# BaseMod.net
KiCad netlist of a schematic drawn in Altium Designer
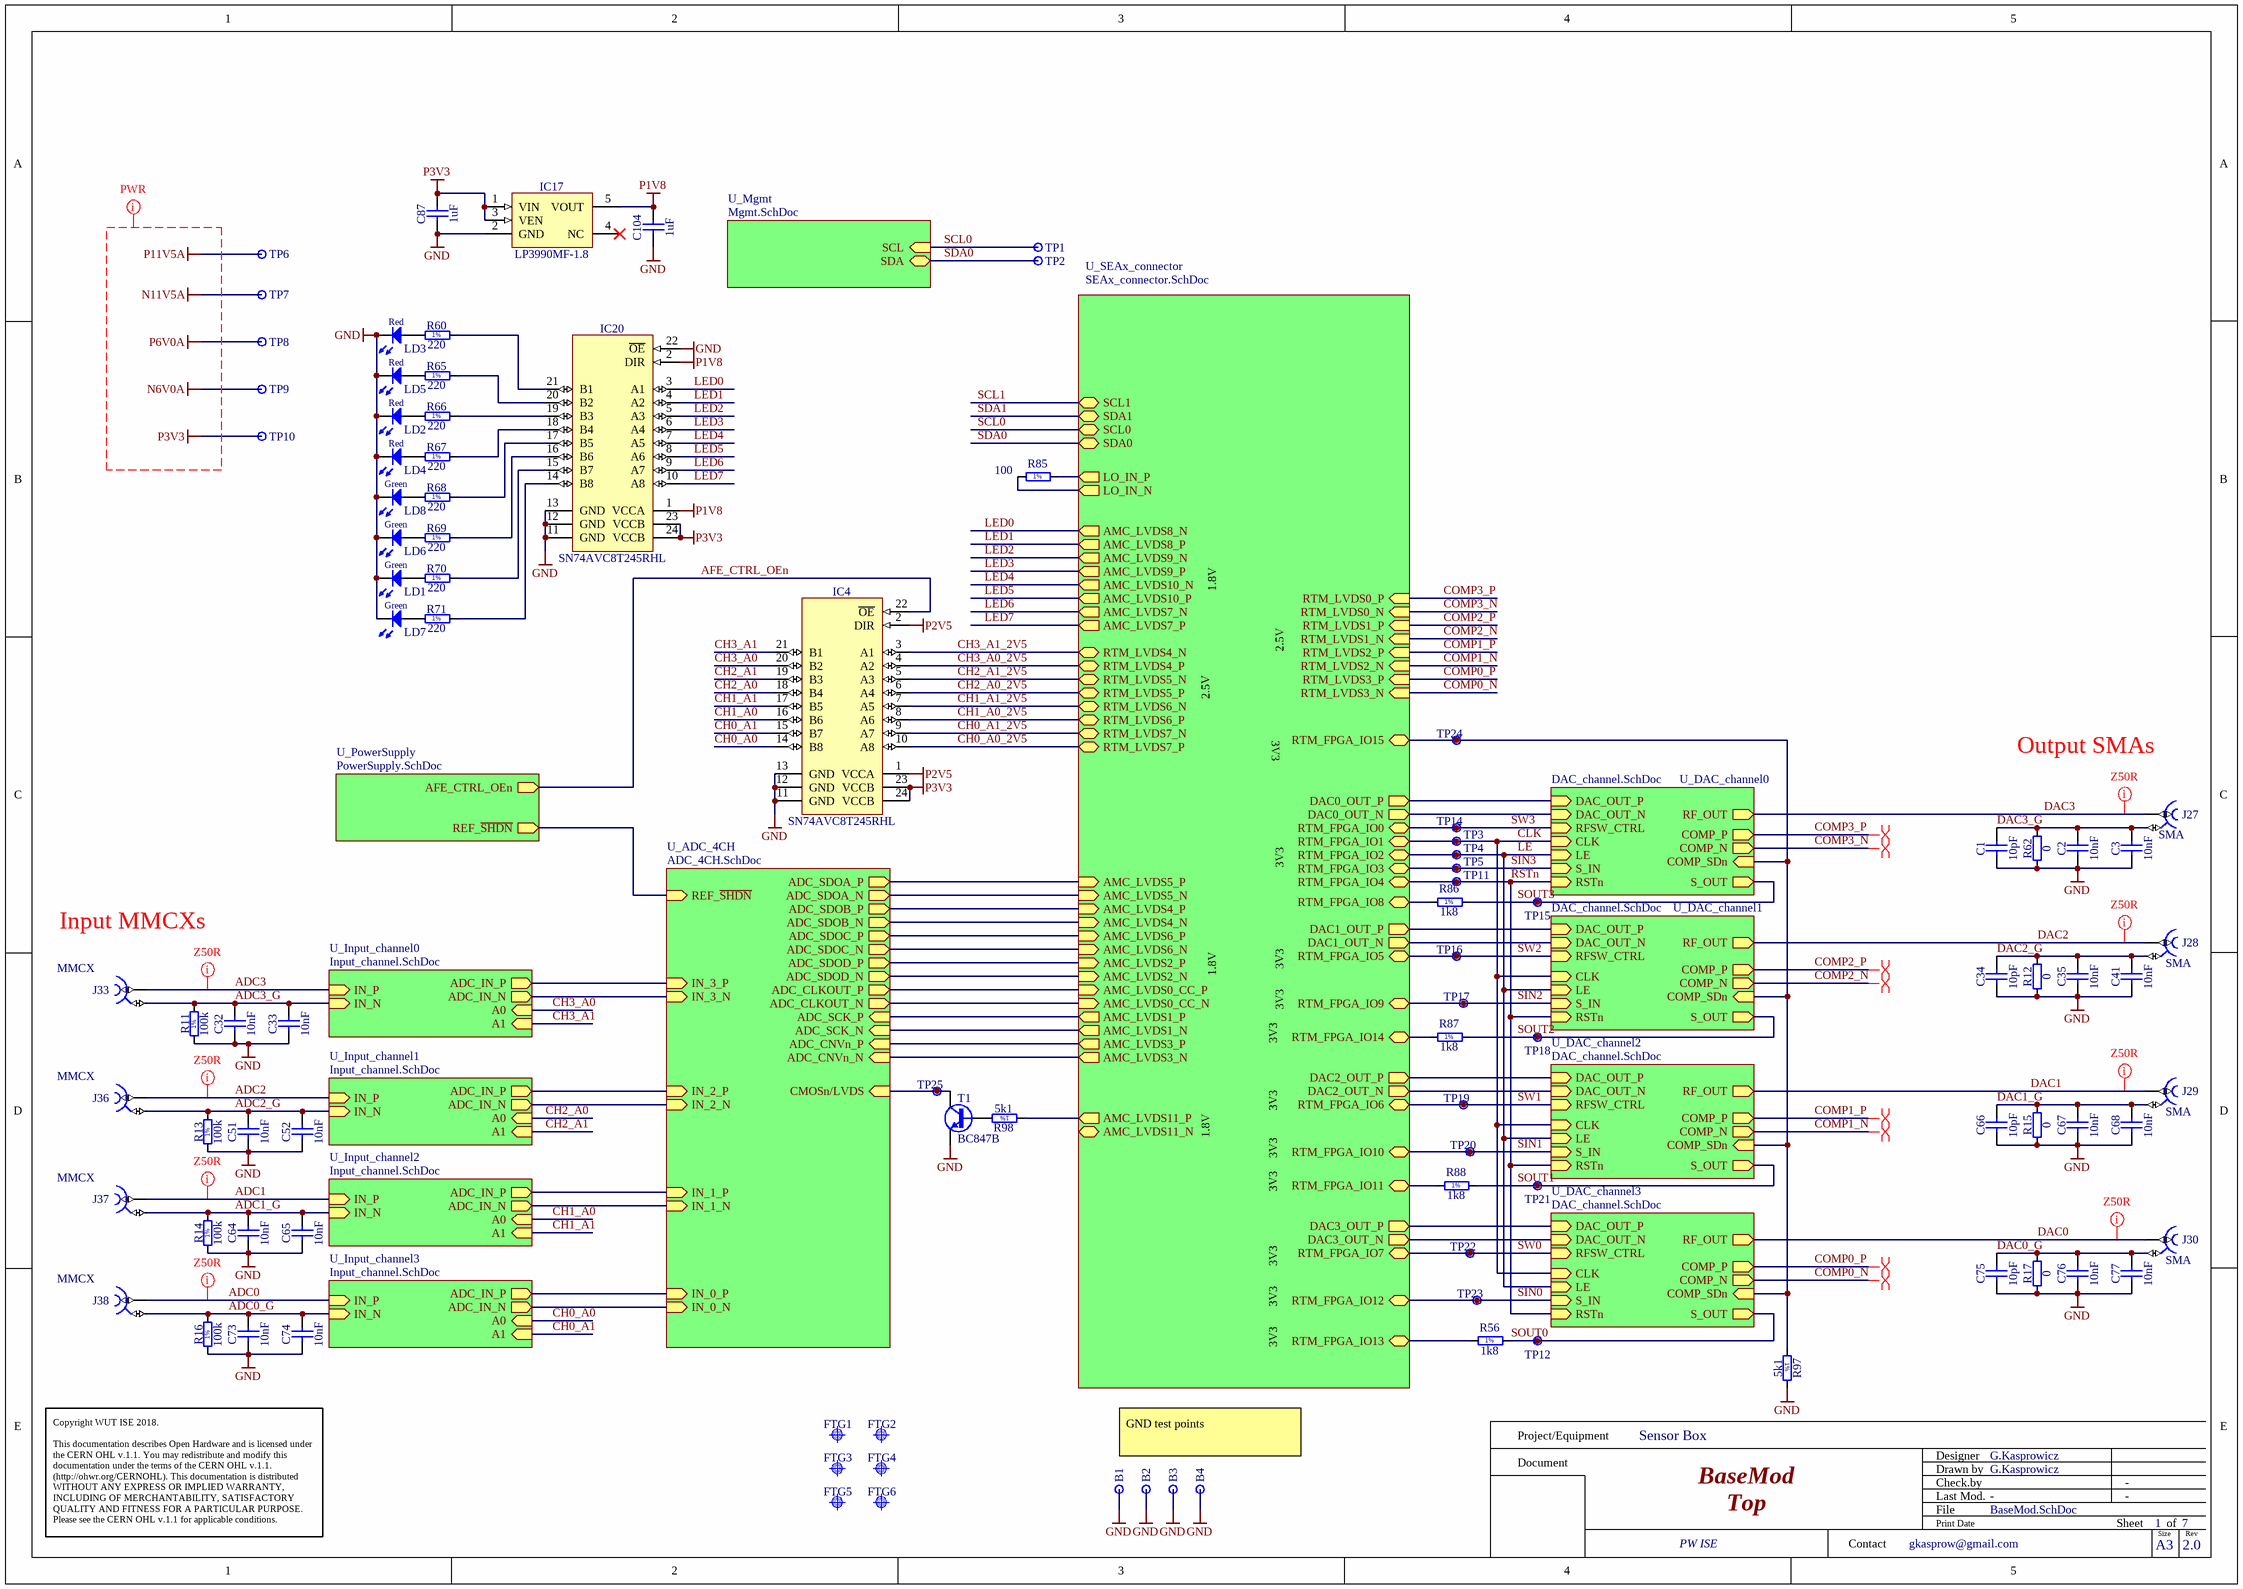
[diagram p0: BaseMod.SchDoc]

(export (version "E")
  (design (tool "Eeschema 10.0.6"))
  (components
    (comp (ref "B1")
      (value "Plated Hole")
      (footprint "c130h80")
      (description "Single Terminal Socket")
      (fields (field (name "PART NUMBER") "PLATED_HOLE0.8_PAD1.3") (field (name "AUTHOR") "CERN DEM JLC"))
      (libsource (lib "Eletro-mechanical") (part "Single Terminal Socket"))
    )
    (comp (ref "B2")
      (value "Plated Hole")
      (footprint "c130h80")
      (description "Single Terminal Socket")
      (fields (field (name "PART NUMBER") "PLATED_HOLE0.8_PAD1.3") (field (name "AUTHOR") "CERN DEM JLC"))
      (libsource (lib "Eletro-mechanical") (part "Single Terminal Socket"))
    )
    (comp (ref "B3")
      (value "Plated Hole")
      (footprint "c130h80")
      (description "Single Terminal Socket")
      (fields (field (name "PART NUMBER") "PLATED_HOLE0.8_PAD1.3") (field (name "AUTHOR") "CERN DEM JLC"))
      (libsource (lib "Eletro-mechanical") (part "Single Terminal Socket"))
    )
    (comp (ref "B4")
      (value "Plated Hole")
      (footprint "c130h80")
      (description "Single Terminal Socket")
      (fields (field (name "PART NUMBER") "PLATED_HOLE0.8_PAD1.3") (field (name "AUTHOR") "CERN DEM JLC"))
      (libsource (lib "Eletro-mechanical") (part "Single Terminal Socket"))
    )
    (comp (ref "C1")
      (value "10pF")
      (footprint "CAPC1005X55N")
      (description "Non-polarised capacitor")
      (fields
        (field (name "PART NUMBER") "CC0402_10PF_50V_5%_C0G")
        (field (name "VOLTAGE") "50V")
        (field (name "AUTHOR") "CERN DEM JLC")
      )
      (libsource (lib "Capacitors") (part "Capacitor - non polarized"))
    )
    (comp (ref "C2")
      (value "10nF")
      (footprint "CAPC1005X55N")
      (description "Non-polarised capacitor")
      (fields
        (field (name "PART NUMBER") "CC0402_10NF_16V_10%_X7R")
        (field (name "VOLTAGE") "16V")
        (field (name "AUTHOR") "CERN DEM JLC")
      )
      (libsource (lib "Capacitors") (part "Capacitor - non polarized"))
    )
    (comp (ref "C3")
      (value "10nF")
      (footprint "CAPC1005X55N")
      (description "Non-polarised capacitor")
      (fields
        (field (name "PART NUMBER") "CC0402_10NF_16V_10%_X7R")
        (field (name "VOLTAGE") "16V")
        (field (name "AUTHOR") "CERN DEM JLC")
      )
      (libsource (lib "Capacitors") (part "Capacitor - non polarized"))
    )
    (comp (ref "C32")
      (value "10nF")
      (footprint "CAPC1005X55N")
      (description "Non-polarised capacitor")
      (fields
        (field (name "PART NUMBER") "CC0402_10NF_16V_10%_X7R")
        (field (name "VOLTAGE") "16V")
        (field (name "AUTHOR") "CERN DEM JLC")
      )
      (libsource (lib "Capacitors") (part "Capacitor - non polarized"))
    )
    (comp (ref "C33")
      (value "10nF")
      (footprint "CAPC1005X55N")
      (description "Non-polarised capacitor")
      (fields
        (field (name "PART NUMBER") "CC0402_10NF_16V_10%_X7R")
        (field (name "VOLTAGE") "16V")
        (field (name "AUTHOR") "CERN DEM JLC")
      )
      (libsource (lib "Capacitors") (part "Capacitor - non polarized"))
    )
    (comp (ref "C34")
      (value "10pF")
      (footprint "CAPC1005X55N")
      (description "Non-polarised capacitor")
      (fields
        (field (name "PART NUMBER") "CC0402_10PF_50V_5%_C0G")
        (field (name "VOLTAGE") "50V")
        (field (name "AUTHOR") "CERN DEM JLC")
      )
      (libsource (lib "Capacitors") (part "Capacitor - non polarized"))
    )
    (comp (ref "C35")
      (value "10nF")
      (footprint "CAPC1005X55N")
      (description "Non-polarised capacitor")
      (fields
        (field (name "PART NUMBER") "CC0402_10NF_16V_10%_X7R")
        (field (name "VOLTAGE") "16V")
        (field (name "AUTHOR") "CERN DEM JLC")
      )
      (libsource (lib "Capacitors") (part "Capacitor - non polarized"))
    )
    (comp (ref "C41")
      (value "10nF")
      (footprint "CAPC1005X55N")
      (description "Non-polarised capacitor")
      (fields
        (field (name "PART NUMBER") "CC0402_10NF_16V_10%_X7R")
        (field (name "VOLTAGE") "16V")
        (field (name "AUTHOR") "CERN DEM JLC")
      )
      (libsource (lib "Capacitors") (part "Capacitor - non polarized"))
    )
    (comp (ref "C51")
      (value "10nF")
      (footprint "CAPC1005X55N")
      (description "Non-polarised capacitor")
      (fields
        (field (name "PART NUMBER") "CC0402_10NF_16V_10%_X7R")
        (field (name "VOLTAGE") "16V")
        (field (name "AUTHOR") "CERN DEM JLC")
      )
      (libsource (lib "Capacitors") (part "Capacitor - non polarized"))
    )
    (comp (ref "C52")
      (value "10nF")
      (footprint "CAPC1005X55N")
      (description "Non-polarised capacitor")
      (fields
        (field (name "PART NUMBER") "CC0402_10NF_16V_10%_X7R")
        (field (name "VOLTAGE") "16V")
        (field (name "AUTHOR") "CERN DEM JLC")
      )
      (libsource (lib "Capacitors") (part "Capacitor - non polarized"))
    )
    (comp (ref "C64")
      (value "10nF")
      (footprint "CAPC1005X55N")
      (description "Non-polarised capacitor")
      (fields
        (field (name "PART NUMBER") "CC0402_10NF_16V_10%_X7R")
        (field (name "VOLTAGE") "16V")
        (field (name "AUTHOR") "CERN DEM JLC")
      )
      (libsource (lib "Capacitors") (part "Capacitor - non polarized"))
    )
    (comp (ref "C65")
      (value "10nF")
      (footprint "CAPC1005X55N")
      (description "Non-polarised capacitor")
      (fields
        (field (name "PART NUMBER") "CC0402_10NF_16V_10%_X7R")
        (field (name "VOLTAGE") "16V")
        (field (name "AUTHOR") "CERN DEM JLC")
      )
      (libsource (lib "Capacitors") (part "Capacitor - non polarized"))
    )
    (comp (ref "C66")
      (value "10pF")
      (footprint "CAPC1005X55N")
      (description "Non-polarised capacitor")
      (fields
        (field (name "PART NUMBER") "CC0402_10PF_50V_5%_C0G")
        (field (name "VOLTAGE") "50V")
        (field (name "AUTHOR") "CERN DEM JLC")
      )
      (libsource (lib "Capacitors") (part "Capacitor - non polarized"))
    )
    (comp (ref "C67")
      (value "10nF")
      (footprint "CAPC1005X55N")
      (description "Non-polarised capacitor")
      (fields
        (field (name "PART NUMBER") "CC0402_10NF_16V_10%_X7R")
        (field (name "VOLTAGE") "16V")
        (field (name "AUTHOR") "CERN DEM JLC")
      )
      (libsource (lib "Capacitors") (part "Capacitor - non polarized"))
    )
    (comp (ref "C68")
      (value "10nF")
      (footprint "CAPC1005X55N")
      (description "Non-polarised capacitor")
      (fields
        (field (name "PART NUMBER") "CC0402_10NF_16V_10%_X7R")
        (field (name "VOLTAGE") "16V")
        (field (name "AUTHOR") "CERN DEM JLC")
      )
      (libsource (lib "Capacitors") (part "Capacitor - non polarized"))
    )
    (comp (ref "C73")
      (value "10nF")
      (footprint "CAPC1005X55N")
      (description "Non-polarised capacitor")
      (fields
        (field (name "PART NUMBER") "CC0402_10NF_16V_10%_X7R")
        (field (name "VOLTAGE") "16V")
        (field (name "AUTHOR") "CERN DEM JLC")
      )
      (libsource (lib "Capacitors") (part "Capacitor - non polarized"))
    )
    (comp (ref "C74")
      (value "10nF")
      (footprint "CAPC1005X55N")
      (description "Non-polarised capacitor")
      (fields
        (field (name "PART NUMBER") "CC0402_10NF_16V_10%_X7R")
        (field (name "VOLTAGE") "16V")
        (field (name "AUTHOR") "CERN DEM JLC")
      )
      (libsource (lib "Capacitors") (part "Capacitor - non polarized"))
    )
    (comp (ref "C75")
      (value "10pF")
      (footprint "CAPC1005X55N")
      (description "Non-polarised capacitor")
      (fields
        (field (name "PART NUMBER") "CC0402_10PF_50V_5%_C0G")
        (field (name "VOLTAGE") "50V")
        (field (name "AUTHOR") "CERN DEM JLC")
      )
      (libsource (lib "Capacitors") (part "Capacitor - non polarized"))
    )
    (comp (ref "C76")
      (value "10nF")
      (footprint "CAPC1005X55N")
      (description "Non-polarised capacitor")
      (fields
        (field (name "PART NUMBER") "CC0402_10NF_16V_10%_X7R")
        (field (name "VOLTAGE") "16V")
        (field (name "AUTHOR") "CERN DEM JLC")
      )
      (libsource (lib "Capacitors") (part "Capacitor - non polarized"))
    )
    (comp (ref "C77")
      (value "10nF")
      (footprint "CAPC1005X55N")
      (description "Non-polarised capacitor")
      (fields
        (field (name "PART NUMBER") "CC0402_10NF_16V_10%_X7R")
        (field (name "VOLTAGE") "16V")
        (field (name "AUTHOR") "CERN DEM JLC")
      )
      (libsource (lib "Capacitors") (part "Capacitor - non polarized"))
    )
    (comp (ref "C87")
      (value "1uF")
      (footprint "CAPC1608X87N")
      (description "Non-polarised capacitor")
      (fields
        (field (name "PART NUMBER") "CC0603_1UF_25V_10%_X7R")
        (field (name "VOLTAGE") "25V")
        (field (name "AUTHOR") "CERN DEM JLC")
      )
      (libsource (lib "Capacitors") (part "Capacitor - non polarized"))
    )
    (comp (ref "C104")
      (value "1uF")
      (footprint "CAPC1608X87N")
      (description "Non-polarised capacitor")
      (fields
        (field (name "PART NUMBER") "CC0603_1UF_25V_10%_X7R")
        (field (name "VOLTAGE") "25V")
        (field (name "AUTHOR") "CERN DEM JLC")
      )
      (libsource (lib "Capacitors") (part "Capacitor - non polarized"))
    )
    (comp (ref "FTG1")
      (value "Use only in PCB")
      (footprint "FIDUCIAL_TOP_C100-200")
      (description "Fiducial Target")
      (fields (field (name "PART NUMBER") "FIDUCIAL_TARGET_C100-200") (field (name "AUTHOR") "CERN DEM JLC"))
      (libsource (lib "Eletro-mechanical") (part "Fiducial Target"))
    )
    (comp (ref "FTG2")
      (value "Use only in PCB")
      (footprint "FIDUCIAL_TOP_S100-200")
      (description "Fiducial Target")
      (fields (field (name "PART NUMBER") "FIDUCIAL_TARGET_S100-200") (field (name "AUTHOR") "CERN DEM JLC"))
      (libsource (lib "Eletro-mechanical") (part "Fiducial Target"))
    )
    (comp (ref "FTG3")
      (value "Use only in PCB")
      (footprint "FIDUCIAL_TOP_C100-200")
      (description "Fiducial Target")
      (fields (field (name "PART NUMBER") "FIDUCIAL_TARGET_C100-200") (field (name "AUTHOR") "CERN DEM JLC"))
      (libsource (lib "Eletro-mechanical") (part "Fiducial Target"))
    )
    (comp (ref "FTG4")
      (value "Use only in PCB")
      (footprint "FIDUCIAL_TOP_S100-200")
      (description "Fiducial Target")
      (fields (field (name "PART NUMBER") "FIDUCIAL_TARGET_S100-200") (field (name "AUTHOR") "CERN DEM JLC"))
      (libsource (lib "Eletro-mechanical") (part "Fiducial Target"))
    )
    (comp (ref "FTG5")
      (value "Use only in PCB")
      (footprint "FIDUCIAL_TOP_C100-200")
      (description "Fiducial Target")
      (fields (field (name "PART NUMBER") "FIDUCIAL_TARGET_C100-200") (field (name "AUTHOR") "CERN DEM JLC"))
      (libsource (lib "Eletro-mechanical") (part "Fiducial Target"))
    )
    (comp (ref "FTG6")
      (value "Use only in PCB")
      (footprint "FIDUCIAL_TOP_S100-200")
      (description "Fiducial Target")
      (fields (field (name "PART NUMBER") "FIDUCIAL_TARGET_S100-200") (field (name "AUTHOR") "CERN DEM JLC"))
      (libsource (lib "Eletro-mechanical") (part "Fiducial Target"))
    )
    (comp (ref "IC4")
      (value "SN74AVC8T245RHL")
      (footprint "TEXAS_RHL (S-PVQFN-N24)")
      (description "8-Bit Dual-Supply Bus Transceiver With Configurable Voltage Translation and 3-State Outputs")
      (fields (field (name "MANUFACTURER") "TEXAS INSTRUMENTS") (field (name "AUTHOR") "CERN DEM MR"))
      (libsource (lib "ICs And Semiconductors") (part "748T245"))
    )
    (comp (ref "IC17")
      (value "LP3990MF-1.8")
      (footprint "SOT95P284X122-5N")
      (description "1.8V, 150mA Linear Voltage Regulator For Digital Applications")
      (fields (field (name "MANUFACTURER") "TEXAS INSTRUMENTS") (field (name "AUTHOR") "CERN DEM JLC"))
      (libsource (lib "ICs And Semiconductors") (part "LP3990MF"))
    )
    (comp (ref "IC20")
      (value "SN74AVC8T245RHL")
      (footprint "TEXAS_RHL (S-PVQFN-N24)")
      (description "8-Bit Dual-Supply Bus Transceiver With Configurable Voltage Translation and 3-State Outputs")
      (fields (field (name "MANUFACTURER") "TEXAS INSTRUMENTS") (field (name "AUTHOR") "CERN DEM MR"))
      (libsource (lib "ICs And Semiconductors") (part "748T245"))
    )
    (comp (ref "J27")
      (value "SMA")
      (footprint "AMPHENOL_901-143_IN BOARD")
      (description "AMPHENOL_901-143")
      (fields
        (field (name "MANUFACTURER") "AMPHENOL")
        (field (name "MANUFACTURER PART NUMBER") "901-143")
        (field (name "AUTHOR") "LNLS DIG GBMB")
      )
      (libsource (lib "LIBRARY_SCH") (part "CON_SMA_RA_AMP"))
    )
    (comp (ref "J28")
      (value "SMA")
      (footprint "AMPHENOL_901-143_IN BOARD")
      (description "AMPHENOL_901-143")
      (fields
        (field (name "MANUFACTURER") "AMPHENOL")
        (field (name "MANUFACTURER PART NUMBER") "901-143")
        (field (name "AUTHOR") "LNLS DIG GBMB")
      )
      (libsource (lib "LIBRARY_SCH") (part "CON_SMA_RA_AMP"))
    )
    (comp (ref "J29")
      (value "SMA")
      (footprint "AMPHENOL_901-143_IN BOARD")
      (description "AMPHENOL_901-143")
      (fields
        (field (name "MANUFACTURER") "AMPHENOL")
        (field (name "MANUFACTURER PART NUMBER") "901-143")
        (field (name "AUTHOR") "LNLS DIG GBMB")
      )
      (libsource (lib "LIBRARY_SCH") (part "CON_SMA_RA_AMP"))
    )
    (comp (ref "J30")
      (value "SMA")
      (footprint "AMPHENOL_901-143_IN BOARD")
      (description "AMPHENOL_901-143")
      (fields
        (field (name "MANUFACTURER") "AMPHENOL")
        (field (name "MANUFACTURER PART NUMBER") "901-143")
        (field (name "AUTHOR") "LNLS DIG GBMB")
      )
      (libsource (lib "LIBRARY_SCH") (part "CON_SMA_RA_AMP"))
    )
    (comp (ref "J33")
      (value "Coax_1Female_1Shield")
      (footprint "HUBER-SUHNER_85_MMCX-50-0-1/111_OE")
      (fields
        (field (name "PART NUMBER") "HUBER-SUHNER_85_MMCX-50-0-1/111_OE")
        (field (name "FAMILY") "MMCX")
        (field (name "MANUFACTURER") "HUBER+SUHNER")
        (field (name "MANUFACTURER PART NUMBER") "85_MMCX-50-0-1/111_OE")
        (field (name "AUTHOR") "CERN DEM JLC")
      )
      (libsource (lib "Connectors") (part "Coax_1Female_1Shield"))
    )
    (comp (ref "J36")
      (value "Coax_1Female_1Shield")
      (footprint "HUBER-SUHNER_85_MMCX-50-0-1/111_OE")
      (fields
        (field (name "PART NUMBER") "HUBER-SUHNER_85_MMCX-50-0-1/111_OE")
        (field (name "FAMILY") "MMCX")
        (field (name "MANUFACTURER") "HUBER+SUHNER")
        (field (name "MANUFACTURER PART NUMBER") "85_MMCX-50-0-1/111_OE")
        (field (name "AUTHOR") "CERN DEM JLC")
      )
      (libsource (lib "Connectors") (part "Coax_1Female_1Shield"))
    )
    (comp (ref "J37")
      (value "Coax_1Female_1Shield")
      (footprint "HUBER-SUHNER_85_MMCX-50-0-1/111_OE")
      (fields
        (field (name "PART NUMBER") "HUBER-SUHNER_85_MMCX-50-0-1/111_OE")
        (field (name "FAMILY") "MMCX")
        (field (name "MANUFACTURER") "HUBER+SUHNER")
        (field (name "MANUFACTURER PART NUMBER") "85_MMCX-50-0-1/111_OE")
        (field (name "AUTHOR") "CERN DEM JLC")
      )
      (libsource (lib "Connectors") (part "Coax_1Female_1Shield"))
    )
    (comp (ref "J38")
      (value "Coax_1Female_1Shield")
      (footprint "HUBER-SUHNER_85_MMCX-50-0-1/111_OE")
      (fields
        (field (name "PART NUMBER") "HUBER-SUHNER_85_MMCX-50-0-1/111_OE")
        (field (name "FAMILY") "MMCX")
        (field (name "MANUFACTURER") "HUBER+SUHNER")
        (field (name "MANUFACTURER PART NUMBER") "85_MMCX-50-0-1/111_OE")
        (field (name "AUTHOR") "CERN DEM JLC")
      )
      (libsource (lib "Connectors") (part "Coax_1Female_1Shield"))
    )
    (comp (ref "LD1")
      (value "Green")
      (footprint "LED_KINGBRIGHT_L-13GD")
      (description "LED Green 2mm")
      (fields
        (field (name "PART NUMBER") "LED_KINGBRIGHT_L-13GD")
        (field (name "MANUFACTURER") "KINGBRIGHT")
        (field (name "AUTHOR") "GK")
      )
      (libsource (lib "LIBRARY_SCH") (part "LED_2mm_RA_Green"))
    )
    (comp (ref "LD2")
      (value "Red")
      (footprint "LED_KINGBRIGHT_L-13ID")
      (description "LED Red 2mm")
      (fields
        (field (name "PART NUMBER") "LED_KINGBRIGHT_L-13ID")
        (field (name "MANUFACTURER") "KINGBRIGHT")
        (field (name "AUTHOR") "GK")
      )
      (libsource (lib "LIBRARY_SCH") (part "LED_2mm_RA_Red"))
    )
    (comp (ref "LD3")
      (value "Red")
      (footprint "LED_KINGBRIGHT_L-13ID")
      (description "LED Red 2mm")
      (fields
        (field (name "PART NUMBER") "LED_KINGBRIGHT_L-13ID")
        (field (name "MANUFACTURER") "KINGBRIGHT")
        (field (name "AUTHOR") "GK")
      )
      (libsource (lib "LIBRARY_SCH") (part "LED_2mm_RA_Red"))
    )
    (comp (ref "LD4")
      (value "Red")
      (footprint "LED_KINGBRIGHT_L-13ID")
      (description "LED Red 2mm")
      (fields
        (field (name "PART NUMBER") "LED_KINGBRIGHT_L-13ID")
        (field (name "MANUFACTURER") "KINGBRIGHT")
        (field (name "AUTHOR") "GK")
      )
      (libsource (lib "LIBRARY_SCH") (part "LED_2mm_RA_Red"))
    )
    (comp (ref "LD5")
      (value "Red")
      (footprint "LED_KINGBRIGHT_L-13ID")
      (description "LED Red 2mm")
      (fields
        (field (name "PART NUMBER") "LED_KINGBRIGHT_L-13ID")
        (field (name "MANUFACTURER") "KINGBRIGHT")
        (field (name "AUTHOR") "GK")
      )
      (libsource (lib "LIBRARY_SCH") (part "LED_2mm_RA_Red"))
    )
    (comp (ref "LD6")
      (value "Green")
      (footprint "LED_KINGBRIGHT_L-13GD")
      (description "LED Green 2mm")
      (fields
        (field (name "PART NUMBER") "LED_KINGBRIGHT_L-13GD")
        (field (name "MANUFACTURER") "KINGBRIGHT")
        (field (name "AUTHOR") "GK")
      )
      (libsource (lib "LIBRARY_SCH") (part "LED_2mm_RA_Green"))
    )
    (comp (ref "LD7")
      (value "Green")
      (footprint "LED_KINGBRIGHT_L-13GD")
      (description "LED Green 2mm")
      (fields
        (field (name "PART NUMBER") "LED_KINGBRIGHT_L-13GD")
        (field (name "MANUFACTURER") "KINGBRIGHT")
        (field (name "AUTHOR") "GK")
      )
      (libsource (lib "LIBRARY_SCH") (part "LED_2mm_RA_Green"))
    )
    (comp (ref "LD8")
      (value "Green")
      (footprint "LED_KINGBRIGHT_L-13GD")
      (description "LED Green 2mm")
      (fields
        (field (name "PART NUMBER") "LED_KINGBRIGHT_L-13GD")
        (field (name "MANUFACTURER") "KINGBRIGHT")
        (field (name "AUTHOR") "GK")
      )
      (libsource (lib "LIBRARY_SCH") (part "LED_2mm_RA_Green"))
    )
    (comp (ref "R11")
      (value "100k")
      (footprint "RESC1608X55N")
      (description "Resistor - 1%")
      (fields
        (field (name "PART NUMBER") "R0603_100K_1%_0.1W_100PPM")
        (field (name "MANUFACTURER") "GENERIC")
        (field (name "AUTHOR") "CERN DEM JLC")
      )
      (libsource (lib "Resistors") (part "Resistor - 1%"))
    )
    (comp (ref "R12")
      (value "0")
      (footprint "RESC1608X55N")
      (description "Resistor")
      (fields
        (field (name "PART NUMBER") "R0603_0R_JUMPER")
        (field (name "MANUFACTURER") "GENERIC")
        (field (name "AUTHOR") "CERN DEM JLC")
      )
      (libsource (lib "Resistors") (part "Resistor"))
    )
    (comp (ref "R13")
      (value "100k")
      (footprint "RESC1608X55N")
      (description "Resistor - 1%")
      (fields
        (field (name "PART NUMBER") "R0603_100K_1%_0.1W_100PPM")
        (field (name "MANUFACTURER") "GENERIC")
        (field (name "AUTHOR") "CERN DEM JLC")
      )
      (libsource (lib "Resistors") (part "Resistor - 1%"))
    )
    (comp (ref "R14")
      (value "100k")
      (footprint "RESC1608X55N")
      (description "Resistor - 1%")
      (fields
        (field (name "PART NUMBER") "R0603_100K_1%_0.1W_100PPM")
        (field (name "MANUFACTURER") "GENERIC")
        (field (name "AUTHOR") "CERN DEM JLC")
      )
      (libsource (lib "Resistors") (part "Resistor - 1%"))
    )
    (comp (ref "R15")
      (value "0")
      (footprint "RESC1608X55N")
      (description "Resistor")
      (fields
        (field (name "PART NUMBER") "R0603_0R_JUMPER")
        (field (name "MANUFACTURER") "GENERIC")
        (field (name "AUTHOR") "CERN DEM JLC")
      )
      (libsource (lib "Resistors") (part "Resistor"))
    )
    (comp (ref "R16")
      (value "100k")
      (footprint "RESC1608X55N")
      (description "Resistor - 1%")
      (fields
        (field (name "PART NUMBER") "R0603_100K_1%_0.1W_100PPM")
        (field (name "MANUFACTURER") "GENERIC")
        (field (name "AUTHOR") "CERN DEM JLC")
      )
      (libsource (lib "Resistors") (part "Resistor - 1%"))
    )
    (comp (ref "R17")
      (value "0")
      (footprint "RESC1608X55N")
      (description "Resistor")
      (fields
        (field (name "PART NUMBER") "R0603_0R_JUMPER")
        (field (name "MANUFACTURER") "GENERIC")
        (field (name "AUTHOR") "CERN DEM JLC")
      )
      (libsource (lib "Resistors") (part "Resistor"))
    )
    (comp (ref "R56")
      (value "1k8")
      (footprint "RESC1608X55N")
      (description "Resistor - 1%")
      (fields
        (field (name "PART NUMBER") "R0603_1K8_1%_0.1W_100PPM")
        (field (name "POWER") "0.1W")
        (field (name "AUTHOR") "CERN DEM JLC")
      )
      (libsource (lib "Resistors") (part "Resistor - 1%"))
    )
    (comp (ref "R60")
      (value "220")
      (footprint "RESC1005X40N")
      (description "Resistor - 1%")
      (fields
        (field (name "PART NUMBER") "R0402_220R_1%_0.0625W_100PPM")
        (field (name "POWER") "0.0625W")
        (field (name "AUTHOR") "CERN DEM JLC")
      )
      (libsource (lib "Resistors") (part "Resistor - 1%"))
    )
    (comp (ref "R62")
      (value "0")
      (footprint "RESC1608X55N")
      (description "Resistor")
      (fields
        (field (name "PART NUMBER") "R0603_0R_JUMPER")
        (field (name "MANUFACTURER") "GENERIC")
        (field (name "AUTHOR") "CERN DEM JLC")
      )
      (libsource (lib "Resistors") (part "Resistor"))
    )
    (comp (ref "R65")
      (value "220")
      (footprint "RESC1005X40N")
      (description "Resistor - 1%")
      (fields
        (field (name "PART NUMBER") "R0402_220R_1%_0.0625W_100PPM")
        (field (name "POWER") "0.0625W")
        (field (name "AUTHOR") "CERN DEM JLC")
      )
      (libsource (lib "Resistors") (part "Resistor - 1%"))
    )
    (comp (ref "R66")
      (value "220")
      (footprint "RESC1005X40N")
      (description "Resistor - 1%")
      (fields
        (field (name "PART NUMBER") "R0402_220R_1%_0.0625W_100PPM")
        (field (name "POWER") "0.0625W")
        (field (name "AUTHOR") "CERN DEM JLC")
      )
      (libsource (lib "Resistors") (part "Resistor - 1%"))
    )
    (comp (ref "R67")
      (value "220")
      (footprint "RESC1005X40N")
      (description "Resistor - 1%")
      (fields
        (field (name "PART NUMBER") "R0402_220R_1%_0.0625W_100PPM")
        (field (name "POWER") "0.0625W")
        (field (name "AUTHOR") "CERN DEM JLC")
      )
      (libsource (lib "Resistors") (part "Resistor - 1%"))
    )
    (comp (ref "R68")
      (value "220")
      (footprint "RESC1005X40N")
      (description "Resistor - 1%")
      (fields
        (field (name "PART NUMBER") "R0402_220R_1%_0.0625W_100PPM")
        (field (name "POWER") "0.0625W")
        (field (name "AUTHOR") "CERN DEM JLC")
      )
      (libsource (lib "Resistors") (part "Resistor - 1%"))
    )
    (comp (ref "R69")
      (value "220")
      (footprint "RESC1005X40N")
      (description "Resistor - 1%")
      (fields
        (field (name "PART NUMBER") "R0402_220R_1%_0.0625W_100PPM")
        (field (name "POWER") "0.0625W")
        (field (name "AUTHOR") "CERN DEM JLC")
      )
      (libsource (lib "Resistors") (part "Resistor - 1%"))
    )
    (comp (ref "R70")
      (value "220")
      (footprint "RESC1005X40N")
      (description "Resistor - 1%")
      (fields
        (field (name "PART NUMBER") "R0402_220R_1%_0.0625W_100PPM")
        (field (name "POWER") "0.0625W")
        (field (name "AUTHOR") "CERN DEM JLC")
      )
      (libsource (lib "Resistors") (part "Resistor - 1%"))
    )
    (comp (ref "R71")
      (value "220")
      (footprint "RESC1005X40N")
      (description "Resistor - 1%")
      (fields
        (field (name "PART NUMBER") "R0402_220R_1%_0.0625W_100PPM")
        (field (name "POWER") "0.0625W")
        (field (name "AUTHOR") "CERN DEM JLC")
      )
      (libsource (lib "Resistors") (part "Resistor - 1%"))
    )
    (comp (ref "R85")
      (value "100")
      (footprint "RESC1005X40N")
      (description "Resistor - 1%")
      (fields
        (field (name "PART NUMBER") "R0402_100R_1%_0.1W_100PPM")
        (field (name "POWER") "0.1W")
        (field (name "AUTHOR") "CERN DEM JLC")
      )
      (libsource (lib "Resistors") (part "Resistor - 1%"))
    )
    (comp (ref "R86")
      (value "1k8")
      (footprint "RESC1608X55N")
      (description "Resistor - 1%")
      (fields
        (field (name "PART NUMBER") "R0603_1K8_1%_0.1W_100PPM")
        (field (name "POWER") "0.1W")
        (field (name "AUTHOR") "CERN DEM JLC")
      )
      (libsource (lib "Resistors") (part "Resistor - 1%"))
    )
    (comp (ref "R87")
      (value "1k8")
      (footprint "RESC1608X55N")
      (description "Resistor - 1%")
      (fields
        (field (name "PART NUMBER") "R0603_1K8_1%_0.1W_100PPM")
        (field (name "POWER") "0.1W")
        (field (name "AUTHOR") "CERN DEM JLC")
      )
      (libsource (lib "Resistors") (part "Resistor - 1%"))
    )
    (comp (ref "R88")
      (value "1k8")
      (footprint "RESC1608X55N")
      (description "Resistor - 1%")
      (fields
        (field (name "PART NUMBER") "R0603_1K8_1%_0.1W_100PPM")
        (field (name "POWER") "0.1W")
        (field (name "AUTHOR") "CERN DEM JLC")
      )
      (libsource (lib "Resistors") (part "Resistor - 1%"))
    )
    (comp (ref "R97")
      (value "5k1")
      (footprint "RESC1005X40N")
      (description "Resistor - 1%")
      (fields
        (field (name "PART NUMBER") "R0402_5K1_1%_0.0625W_100PPM")
        (field (name "POWER") "0.0625W")
        (field (name "AUTHOR") "CERN DEM JLC")
      )
      (libsource (lib "Resistors") (part "Resistor - 1%"))
    )
    (comp (ref "R98")
      (value "5k1")
      (footprint "RESC1005X40N")
      (description "Resistor - 1%")
      (fields
        (field (name "PART NUMBER") "R0402_5K1_1%_0.0625W_100PPM")
        (field (name "POWER") "0.0625W")
        (field (name "AUTHOR") "CERN DEM JLC")
      )
      (libsource (lib "Resistors") (part "Resistor - 1%"))
    )
    (comp (ref "T1")
      (value "BC847B")
      (footprint "SOT95P230X110-3N")
      (description "NPN Transistor")
      (fields (field (name "MANUFACTURER") "NXP SEMICONDUCTORS") (field (name "AUTHOR") "CERN DEM JLC"))
      (libsource (lib "ICs And Semiconductors") (part "NPN B1 E2 C3"))
    )
    (comp (ref "TP1")
      (value "Test Point")
      (footprint "TPS127")
      (fields (field (name "PART NUMBER") "SMD_PAD_1.27X1.27MM") (field (name "AUTHOR") "CERN DEM JLC"))
      (libsource (lib "Eletro-mechanical") (part "Test Point"))
    )
    (comp (ref "TP2")
      (value "Test Point")
      (footprint "TPS127")
      (fields (field (name "PART NUMBER") "SMD_PAD_1.27X1.27MM") (field (name "AUTHOR") "CERN DEM JLC"))
      (libsource (lib "Eletro-mechanical") (part "Test Point"))
    )
    (comp (ref "TP3")
      (value "Test Point")
      (footprint "TPS127")
      (fields (field (name "PART NUMBER") "SMD_PAD_1.27X1.27MM") (field (name "AUTHOR") "CERN DEM JLC"))
      (libsource (lib "Eletro-mechanical") (part "Test Point"))
    )
    (comp (ref "TP4")
      (value "Test Point")
      (footprint "TPS127")
      (fields (field (name "PART NUMBER") "SMD_PAD_1.27X1.27MM") (field (name "AUTHOR") "CERN DEM JLC"))
      (libsource (lib "Eletro-mechanical") (part "Test Point"))
    )
    (comp (ref "TP5")
      (value "Test Point")
      (footprint "TPS127")
      (fields (field (name "PART NUMBER") "SMD_PAD_1.27X1.27MM") (field (name "AUTHOR") "CERN DEM JLC"))
      (libsource (lib "Eletro-mechanical") (part "Test Point"))
    )
    (comp (ref "TP6")
      (value "Test Point")
      (footprint "TPS127")
      (fields (field (name "PART NUMBER") "SMD_PAD_1.27X1.27MM") (field (name "AUTHOR") "CERN DEM JLC"))
      (libsource (lib "Eletro-mechanical") (part "Test Point"))
    )
    (comp (ref "TP7")
      (value "Test Point")
      (footprint "TPS127")
      (fields (field (name "PART NUMBER") "SMD_PAD_1.27X1.27MM") (field (name "AUTHOR") "CERN DEM JLC"))
      (libsource (lib "Eletro-mechanical") (part "Test Point"))
    )
    (comp (ref "TP8")
      (value "Test Point")
      (footprint "TPS127")
      (fields (field (name "PART NUMBER") "SMD_PAD_1.27X1.27MM") (field (name "AUTHOR") "CERN DEM JLC"))
      (libsource (lib "Eletro-mechanical") (part "Test Point"))
    )
    (comp (ref "TP9")
      (value "Test Point")
      (footprint "TPS127")
      (fields (field (name "PART NUMBER") "SMD_PAD_1.27X1.27MM") (field (name "AUTHOR") "CERN DEM JLC"))
      (libsource (lib "Eletro-mechanical") (part "Test Point"))
    )
    (comp (ref "TP10")
      (value "Test Point")
      (footprint "TPS127")
      (fields (field (name "PART NUMBER") "SMD_PAD_1.27X1.27MM") (field (name "AUTHOR") "CERN DEM JLC"))
      (libsource (lib "Eletro-mechanical") (part "Test Point"))
    )
    (comp (ref "TP11")
      (value "Test Point")
      (footprint "TPS127")
      (fields (field (name "PART NUMBER") "SMD_PAD_1.27X1.27MM") (field (name "AUTHOR") "CERN DEM JLC"))
      (libsource (lib "Eletro-mechanical") (part "Test Point"))
    )
    (comp (ref "TP12")
      (value "Test Point")
      (footprint "TPS127")
      (fields (field (name "PART NUMBER") "SMD_PAD_1.27X1.27MM") (field (name "AUTHOR") "CERN DEM JLC"))
      (libsource (lib "Eletro-mechanical") (part "Test Point"))
    )
    (comp (ref "TP14")
      (value "Test Point")
      (footprint "TPS127")
      (fields (field (name "PART NUMBER") "SMD_PAD_1.27X1.27MM") (field (name "AUTHOR") "CERN DEM JLC"))
      (libsource (lib "Eletro-mechanical") (part "Test Point"))
    )
    (comp (ref "TP15")
      (value "Test Point")
      (footprint "TPS127")
      (fields (field (name "PART NUMBER") "SMD_PAD_1.27X1.27MM") (field (name "AUTHOR") "CERN DEM JLC"))
      (libsource (lib "Eletro-mechanical") (part "Test Point"))
    )
    (comp (ref "TP16")
      (value "Test Point")
      (footprint "TPS127")
      (fields (field (name "PART NUMBER") "SMD_PAD_1.27X1.27MM") (field (name "AUTHOR") "CERN DEM JLC"))
      (libsource (lib "Eletro-mechanical") (part "Test Point"))
    )
    (comp (ref "TP17")
      (value "Test Point")
      (footprint "TPS127")
      (fields (field (name "PART NUMBER") "SMD_PAD_1.27X1.27MM") (field (name "AUTHOR") "CERN DEM JLC"))
      (libsource (lib "Eletro-mechanical") (part "Test Point"))
    )
    (comp (ref "TP18")
      (value "Test Point")
      (footprint "TPS127")
      (fields (field (name "PART NUMBER") "SMD_PAD_1.27X1.27MM") (field (name "AUTHOR") "CERN DEM JLC"))
      (libsource (lib "Eletro-mechanical") (part "Test Point"))
    )
    (comp (ref "TP19")
      (value "Test Point")
      (footprint "TPS127")
      (fields (field (name "PART NUMBER") "SMD_PAD_1.27X1.27MM") (field (name "AUTHOR") "CERN DEM JLC"))
      (libsource (lib "Eletro-mechanical") (part "Test Point"))
    )
    (comp (ref "TP20")
      (value "Test Point")
      (footprint "TPS127")
      (fields (field (name "PART NUMBER") "SMD_PAD_1.27X1.27MM") (field (name "AUTHOR") "CERN DEM JLC"))
      (libsource (lib "Eletro-mechanical") (part "Test Point"))
    )
    (comp (ref "TP21")
      (value "Test Point")
      (footprint "TPS127")
      (fields (field (name "PART NUMBER") "SMD_PAD_1.27X1.27MM") (field (name "AUTHOR") "CERN DEM JLC"))
      (libsource (lib "Eletro-mechanical") (part "Test Point"))
    )
    (comp (ref "TP22")
      (value "Test Point")
      (footprint "TPS127")
      (fields (field (name "PART NUMBER") "SMD_PAD_1.27X1.27MM") (field (name "AUTHOR") "CERN DEM JLC"))
      (libsource (lib "Eletro-mechanical") (part "Test Point"))
    )
    (comp (ref "TP23")
      (value "Test Point")
      (footprint "TPS127")
      (fields (field (name "PART NUMBER") "SMD_PAD_1.27X1.27MM") (field (name "AUTHOR") "CERN DEM JLC"))
      (libsource (lib "Eletro-mechanical") (part "Test Point"))
    )
    (comp (ref "TP24")
      (value "Test Point")
      (footprint "TPS127")
      (fields (field (name "PART NUMBER") "SMD_PAD_1.27X1.27MM") (field (name "AUTHOR") "CERN DEM JLC"))
      (libsource (lib "Eletro-mechanical") (part "Test Point"))
    )
    (comp (ref "TP25")
      (value "Test Point")
      (footprint "TPS127")
      (fields (field (name "PART NUMBER") "SMD_PAD_1.27X1.27MM") (field (name "AUTHOR") "CERN DEM JLC"))
      (libsource (lib "Eletro-mechanical") (part "Test Point"))
    )
  )
  (nets
    (net (code "1") (name "/ADC0") (class "Default")
      (node (ref "J38") (pin "1") (pinfunction "1_1") (pintype "bidirectional"))
    )
    (net (code "2") (name "/ADC0_G") (class "Default")
      (node (ref "C73") (pin "2") (pinfunction "2_2") (pintype "passive"))
      (node (ref "C74") (pin "2") (pinfunction "2_2") (pintype "passive"))
      (node (ref "J38") (pin "2") (pinfunction "2_2") (pintype "bidirectional"))
      (node (ref "R16") (pin "2") (pinfunction "2_2") (pintype "passive"))
    )
    (net (code "3") (name "/ADC1") (class "Default")
      (node (ref "J37") (pin "1") (pinfunction "1_1") (pintype "bidirectional"))
    )
    (net (code "4") (name "/ADC1_G") (class "Default")
      (node (ref "C64") (pin "2") (pinfunction "2_2") (pintype "passive"))
      (node (ref "C65") (pin "2") (pinfunction "2_2") (pintype "passive"))
      (node (ref "J37") (pin "2") (pinfunction "2_2") (pintype "bidirectional"))
      (node (ref "R14") (pin "2") (pinfunction "2_2") (pintype "passive"))
    )
    (net (code "5") (name "/ADC2") (class "Default")
      (node (ref "J36") (pin "1") (pinfunction "1_1") (pintype "bidirectional"))
    )
    (net (code "6") (name "/ADC2_G") (class "Default")
      (node (ref "C51") (pin "2") (pinfunction "2_2") (pintype "passive"))
      (node (ref "C52") (pin "2") (pinfunction "2_2") (pintype "passive"))
      (node (ref "J36") (pin "2") (pinfunction "2_2") (pintype "bidirectional"))
      (node (ref "R13") (pin "2") (pinfunction "2_2") (pintype "passive"))
    )
    (net (code "7") (name "/ADC3") (class "Default")
      (node (ref "J33") (pin "1") (pinfunction "1_1") (pintype "bidirectional"))
    )
    (net (code "8") (name "/ADC3_G") (class "Default")
      (node (ref "C32") (pin "2") (pinfunction "2_2") (pintype "passive"))
      (node (ref "C33") (pin "2") (pinfunction "2_2") (pintype "passive"))
      (node (ref "J33") (pin "2") (pinfunction "2_2") (pintype "bidirectional"))
      (node (ref "R11") (pin "2") (pinfunction "2_2") (pintype "passive"))
    )
    (net (code "27") (name "/AFE_CTRL_OEn") (class "Default")
      (node (ref "IC4") (pin "22") (pinfunction "~{OE}_22") (pintype "input"))
    )
    (net (code "33") (name "/AMC_LVDS11_P") (class "Default")
      (node (ref "R98") (pin "1") (pinfunction "1_1") (pintype "passive"))
    )
    (net (code "34") (name "/CH0_A0") (class "Default")
      (node (ref "IC4") (pin "14") (pinfunction "B8_14") (pintype "bidirectional"))
    )
    (net (code "35") (name "/CH0_A0_2V5") (class "Default")
      (node (ref "IC4") (pin "10") (pinfunction "A8_10") (pintype "bidirectional"))
    )
    (net (code "36") (name "/CH0_A1") (class "Default")
      (node (ref "IC4") (pin "15") (pinfunction "B7_15") (pintype "bidirectional"))
    )
    (net (code "37") (name "/CH0_A1_2V5") (class "Default")
      (node (ref "IC4") (pin "9") (pinfunction "A7_9") (pintype "bidirectional"))
    )
    (net (code "38") (name "/CH1_A0") (class "Default")
      (node (ref "IC4") (pin "16") (pinfunction "B6_16") (pintype "bidirectional"))
    )
    (net (code "39") (name "/CH1_A0_2V5") (class "Default")
      (node (ref "IC4") (pin "8") (pinfunction "A6_8") (pintype "bidirectional"))
    )
    (net (code "40") (name "/CH1_A1") (class "Default")
      (node (ref "IC4") (pin "17") (pinfunction "B5_17") (pintype "bidirectional"))
    )
    (net (code "41") (name "/CH1_A1_2V5") (class "Default")
      (node (ref "IC4") (pin "7") (pinfunction "A5_7") (pintype "bidirectional"))
    )
    (net (code "42") (name "/CH2_A0") (class "Default")
      (node (ref "IC4") (pin "18") (pinfunction "B4_18") (pintype "bidirectional"))
    )
    (net (code "43") (name "/CH2_A0_2V5") (class "Default")
      (node (ref "IC4") (pin "6") (pinfunction "A4_6") (pintype "bidirectional"))
    )
    (net (code "44") (name "/CH2_A1") (class "Default")
      (node (ref "IC4") (pin "19") (pinfunction "B3_19") (pintype "bidirectional"))
    )
    (net (code "45") (name "/CH2_A1_2V5") (class "Default")
      (node (ref "IC4") (pin "5") (pinfunction "A3_5") (pintype "bidirectional"))
    )
    (net (code "46") (name "/CH3_A0") (class "Default")
      (node (ref "IC4") (pin "20") (pinfunction "B2_20") (pintype "bidirectional"))
    )
    (net (code "47") (name "/CH3_A0_2V5") (class "Default")
      (node (ref "IC4") (pin "4") (pinfunction "A2_4") (pintype "bidirectional"))
    )
    (net (code "48") (name "/CH3_A1") (class "Default")
      (node (ref "IC4") (pin "21") (pinfunction "B1_21") (pintype "bidirectional"))
    )
    (net (code "49") (name "/CH3_A1_2V5") (class "Default")
      (node (ref "IC4") (pin "3") (pinfunction "A1_3") (pintype "bidirectional"))
    )
    (net (code "50") (name "/CLK") (class "Default")
      (node (ref "TP3") (pin "1") (pinfunction "1_1") (pintype "bidirectional"))
    )
    (net (code "51") (name "/CMOSn{slash}LVDS") (class "Default")
      (node (ref "T1") (pin "3") (pinfunction "C_3") (pintype "passive"))
      (node (ref "TP25") (pin "1") (pinfunction "1_1") (pintype "bidirectional"))
    )
    (net (code "60") (name "/COMP_SDn") (class "Default")
      (node (ref "R97") (pin "1") (pinfunction "1_1") (pintype "passive"))
      (node (ref "TP24") (pin "1") (pinfunction "1_1") (pintype "bidirectional"))
    )
    (net (code "61") (name "/DAC0") (class "Default")
      (node (ref "J30") (pin "1") (pinfunction "1_1") (pintype "bidirectional"))
    )
    (net (code "62") (name "/DAC0_G") (class "Default")
      (node (ref "C75") (pin "2") (pinfunction "2_2") (pintype "passive"))
      (node (ref "C76") (pin "2") (pinfunction "2_2") (pintype "passive"))
      (node (ref "C77") (pin "2") (pinfunction "2_2") (pintype "passive"))
      (node (ref "J30") (pin "2") (pinfunction "2_2") (pintype "bidirectional"))
      (node (ref "R17") (pin "2") (pinfunction "2_2") (pintype "passive"))
    )
    (net (code "65") (name "/DAC1") (class "Default")
      (node (ref "J29") (pin "1") (pinfunction "1_1") (pintype "bidirectional"))
    )
    (net (code "66") (name "/DAC1_G") (class "Default")
      (node (ref "C66") (pin "2") (pinfunction "2_2") (pintype "passive"))
      (node (ref "C67") (pin "2") (pinfunction "2_2") (pintype "passive"))
      (node (ref "C68") (pin "2") (pinfunction "2_2") (pintype "passive"))
      (node (ref "J29") (pin "2") (pinfunction "2_2") (pintype "bidirectional"))
      (node (ref "R15") (pin "2") (pinfunction "2_2") (pintype "passive"))
    )
    (net (code "69") (name "/DAC2") (class "Default")
      (node (ref "J28") (pin "1") (pinfunction "1_1") (pintype "bidirectional"))
    )
    (net (code "70") (name "/DAC2_G") (class "Default")
      (node (ref "C34") (pin "2") (pinfunction "2_2") (pintype "passive"))
      (node (ref "C35") (pin "2") (pinfunction "2_2") (pintype "passive"))
      (node (ref "C41") (pin "2") (pinfunction "2_2") (pintype "passive"))
      (node (ref "J28") (pin "2") (pinfunction "2_2") (pintype "bidirectional"))
      (node (ref "R12") (pin "2") (pinfunction "2_2") (pintype "passive"))
    )
    (net (code "73") (name "/DAC3") (class "Default")
      (node (ref "J27") (pin "1") (pinfunction "1_1") (pintype "bidirectional"))
    )
    (net (code "74") (name "/DAC3_G") (class "Default")
      (node (ref "C1") (pin "2") (pinfunction "2_2") (pintype "passive"))
      (node (ref "C2") (pin "2") (pinfunction "2_2") (pintype "passive"))
      (node (ref "C3") (pin "2") (pinfunction "2_2") (pintype "passive"))
      (node (ref "J27") (pin "2") (pinfunction "2_2") (pintype "bidirectional"))
      (node (ref "R62") (pin "2") (pinfunction "2_2") (pintype "passive"))
    )
    (net (code "77") (name "/LE") (class "Default")
      (node (ref "TP4") (pin "1") (pinfunction "1_1") (pintype "bidirectional"))
    )
    (net (code "78") (name "/LED0") (class "Default")
      (node (ref "IC20") (pin "3") (pinfunction "A1_3") (pintype "bidirectional"))
    )
    (net (code "79") (name "/LED1") (class "Default")
      (node (ref "IC20") (pin "4") (pinfunction "A2_4") (pintype "bidirectional"))
    )
    (net (code "80") (name "/LED2") (class "Default")
      (node (ref "IC20") (pin "5") (pinfunction "A3_5") (pintype "bidirectional"))
    )
    (net (code "81") (name "/LED3") (class "Default")
      (node (ref "IC20") (pin "6") (pinfunction "A4_6") (pintype "bidirectional"))
    )
    (net (code "82") (name "/LED4") (class "Default")
      (node (ref "IC20") (pin "7") (pinfunction "A5_7") (pintype "bidirectional"))
    )
    (net (code "83") (name "/LED5") (class "Default")
      (node (ref "IC20") (pin "8") (pinfunction "A6_8") (pintype "bidirectional"))
    )
    (net (code "84") (name "/LED6") (class "Default")
      (node (ref "IC20") (pin "9") (pinfunction "A7_9") (pintype "bidirectional"))
    )
    (net (code "85") (name "/LED7") (class "Default")
      (node (ref "IC20") (pin "10") (pinfunction "A8_10") (pintype "bidirectional"))
    )
    (net (code "86") (name "/LO_IN_N") (class "Default")
      (node (ref "R85") (pin "1") (pinfunction "1_1") (pintype "passive"))
    )
    (net (code "87") (name "/LO_IN_P") (class "Default")
      (node (ref "R85") (pin "2") (pinfunction "2_2") (pintype "passive"))
    )
    (net (code "89") (name "/RSTn") (class "Default")
      (node (ref "TP11") (pin "1") (pinfunction "1_1") (pintype "bidirectional"))
    )
    (net (code "90") (name "/RTM_FPGA_IO8") (class "Default")
      (node (ref "R86") (pin "1") (pinfunction "1_1") (pintype "passive"))
    )
    (net (code "91") (name "/RTM_FPGA_IO11") (class "Default")
      (node (ref "R88") (pin "1") (pinfunction "1_1") (pintype "passive"))
    )
    (net (code "92") (name "/RTM_FPGA_IO13") (class "Default")
      (node (ref "R56") (pin "1") (pinfunction "1_1") (pintype "passive"))
    )
    (net (code "93") (name "/RTM_FPGA_IO14") (class "Default")
      (node (ref "R87") (pin "1") (pinfunction "1_1") (pintype "passive"))
    )
    (net (code "94") (name "/SCL0") (class "Default")
      (node (ref "TP1") (pin "1") (pinfunction "1_1") (pintype "bidirectional"))
    )
    (net (code "96") (name "/SDA0") (class "Default")
      (node (ref "TP2") (pin "1") (pinfunction "1_1") (pintype "bidirectional"))
    )
    (net (code "98") (name "/SIN0") (class "Default")
      (node (ref "TP23") (pin "1") (pinfunction "1_1") (pintype "bidirectional"))
    )
    (net (code "99") (name "/SIN1") (class "Default")
      (node (ref "TP20") (pin "1") (pinfunction "1_1") (pintype "bidirectional"))
    )
    (net (code "100") (name "/SIN2") (class "Default")
      (node (ref "TP17") (pin "1") (pinfunction "1_1") (pintype "bidirectional"))
    )
    (net (code "101") (name "/SIN3") (class "Default")
      (node (ref "TP5") (pin "1") (pinfunction "1_1") (pintype "bidirectional"))
    )
    (net (code "102") (name "/SOUT0") (class "Default")
      (node (ref "R56") (pin "2") (pinfunction "2_2") (pintype "passive"))
      (node (ref "TP12") (pin "1") (pinfunction "1_1") (pintype "bidirectional"))
    )
    (net (code "103") (name "/SOUT1") (class "Default")
      (node (ref "R88") (pin "2") (pinfunction "2_2") (pintype "passive"))
      (node (ref "TP21") (pin "1") (pinfunction "1_1") (pintype "bidirectional"))
    )
    (net (code "104") (name "/SOUT2") (class "Default")
      (node (ref "R87") (pin "2") (pinfunction "2_2") (pintype "passive"))
      (node (ref "TP18") (pin "1") (pinfunction "1_1") (pintype "bidirectional"))
    )
    (net (code "105") (name "/SOUT3") (class "Default")
      (node (ref "R86") (pin "2") (pinfunction "2_2") (pintype "passive"))
      (node (ref "TP15") (pin "1") (pinfunction "1_1") (pintype "bidirectional"))
    )
    (net (code "106") (name "/SW0") (class "Default")
      (node (ref "TP22") (pin "1") (pinfunction "1_1") (pintype "bidirectional"))
    )
    (net (code "107") (name "/SW1") (class "Default")
      (node (ref "TP19") (pin "1") (pinfunction "1_1") (pintype "bidirectional"))
    )
    (net (code "108") (name "/SW2") (class "Default")
      (node (ref "TP16") (pin "1") (pinfunction "1_1") (pintype "bidirectional"))
    )
    (net (code "109") (name "/SW3") (class "Default")
      (node (ref "TP14") (pin "1") (pinfunction "1_1") (pintype "bidirectional"))
    )
    (net (code "110") (name "GND") (class "Default")
      (node (ref "B1") (pin "1") (pinfunction "1_1") (pintype "bidirectional"))
      (node (ref "B2") (pin "1") (pinfunction "1_1") (pintype "bidirectional"))
      (node (ref "B3") (pin "1") (pinfunction "1_1") (pintype "bidirectional"))
      (node (ref "B4") (pin "1") (pinfunction "1_1") (pintype "bidirectional"))
      (node (ref "C1") (pin "1") (pinfunction "1_1") (pintype "passive"))
      (node (ref "C104") (pin "1") (pinfunction "1_1") (pintype "passive"))
      (node (ref "C2") (pin "1") (pinfunction "1_1") (pintype "passive"))
      (node (ref "C3") (pin "1") (pinfunction "1_1") (pintype "passive"))
      (node (ref "C32") (pin "1") (pinfunction "1_1") (pintype "passive"))
      (node (ref "C33") (pin "1") (pinfunction "1_1") (pintype "passive"))
      (node (ref "C34") (pin "1") (pinfunction "1_1") (pintype "passive"))
      (node (ref "C35") (pin "1") (pinfunction "1_1") (pintype "passive"))
      (node (ref "C41") (pin "1") (pinfunction "1_1") (pintype "passive"))
      (node (ref "C51") (pin "1") (pinfunction "1_1") (pintype "passive"))
      (node (ref "C52") (pin "1") (pinfunction "1_1") (pintype "passive"))
      (node (ref "C64") (pin "1") (pinfunction "1_1") (pintype "passive"))
      (node (ref "C65") (pin "1") (pinfunction "1_1") (pintype "passive"))
      (node (ref "C66") (pin "1") (pinfunction "1_1") (pintype "passive"))
      (node (ref "C67") (pin "1") (pinfunction "1_1") (pintype "passive"))
      (node (ref "C68") (pin "1") (pinfunction "1_1") (pintype "passive"))
      (node (ref "C73") (pin "1") (pinfunction "1_1") (pintype "passive"))
      (node (ref "C74") (pin "1") (pinfunction "1_1") (pintype "passive"))
      (node (ref "C75") (pin "1") (pinfunction "1_1") (pintype "passive"))
      (node (ref "C76") (pin "1") (pinfunction "1_1") (pintype "passive"))
      (node (ref "C77") (pin "1") (pinfunction "1_1") (pintype "passive"))
      (node (ref "C87") (pin "1") (pinfunction "1_1") (pintype "passive"))
      (node (ref "IC17") (pin "2") (pinfunction "GND_2") (pintype "power_in"))
      (node (ref "IC20") (pin "11") (pinfunction "GND_11") (pintype "power_in"))
      (node (ref "IC20") (pin "12") (pinfunction "GND_12") (pintype "power_in"))
      (node (ref "IC20") (pin "13") (pinfunction "GND_13") (pintype "power_in"))
      (node (ref "IC20") (pin "22") (pinfunction "~{OE}_22") (pintype "input"))
      (node (ref "IC4") (pin "11") (pinfunction "GND_11") (pintype "power_in"))
      (node (ref "IC4") (pin "12") (pinfunction "GND_12") (pintype "power_in"))
      (node (ref "IC4") (pin "13") (pinfunction "GND_13") (pintype "power_in"))
      (node (ref "LD1") (pin "1") (pinfunction "C_1") (pintype "passive"))
      (node (ref "LD2") (pin "1") (pinfunction "C_1") (pintype "passive"))
      (node (ref "LD3") (pin "1") (pinfunction "C_1") (pintype "passive"))
      (node (ref "LD4") (pin "1") (pinfunction "C_1") (pintype "passive"))
      (node (ref "LD5") (pin "1") (pinfunction "C_1") (pintype "passive"))
      (node (ref "LD6") (pin "1") (pinfunction "C_1") (pintype "passive"))
      (node (ref "LD7") (pin "1") (pinfunction "C_1") (pintype "passive"))
      (node (ref "LD8") (pin "1") (pinfunction "C_1") (pintype "passive"))
      (node (ref "R11") (pin "1") (pinfunction "1_1") (pintype "passive"))
      (node (ref "R12") (pin "1") (pinfunction "1_1") (pintype "passive"))
      (node (ref "R13") (pin "1") (pinfunction "1_1") (pintype "passive"))
      (node (ref "R14") (pin "1") (pinfunction "1_1") (pintype "passive"))
      (node (ref "R15") (pin "1") (pinfunction "1_1") (pintype "passive"))
      (node (ref "R16") (pin "1") (pinfunction "1_1") (pintype "passive"))
      (node (ref "R17") (pin "1") (pinfunction "1_1") (pintype "passive"))
      (node (ref "R62") (pin "1") (pinfunction "1_1") (pintype "passive"))
      (node (ref "R97") (pin "2") (pinfunction "2_2") (pintype "passive"))
      (node (ref "T1") (pin "2") (pinfunction "E_2") (pintype "passive"))
    )
    (net (code "111") (name "N6V0A") (class "Default")
      (node (ref "TP9") (pin "1") (pinfunction "1_1") (pintype "bidirectional"))
    )
    (net (code "112") (name "N11V5A") (class "Default")
      (node (ref "TP7") (pin "1") (pinfunction "1_1") (pintype "bidirectional"))
    )
    (net (code "113") (name "Net-(IC20-B1)") (class "Default")
      (node (ref "IC20") (pin "21") (pinfunction "B1_21") (pintype "bidirectional"))
      (node (ref "R60") (pin "2") (pinfunction "2_2") (pintype "passive"))
    )
    (net (code "114") (name "Net-(IC20-B2)") (class "Default")
      (node (ref "IC20") (pin "20") (pinfunction "B2_20") (pintype "bidirectional"))
      (node (ref "R65") (pin "2") (pinfunction "2_2") (pintype "passive"))
    )
    (net (code "115") (name "Net-(IC20-B3)") (class "Default")
      (node (ref "IC20") (pin "19") (pinfunction "B3_19") (pintype "bidirectional"))
      (node (ref "R66") (pin "2") (pinfunction "2_2") (pintype "passive"))
    )
    (net (code "116") (name "Net-(IC20-B4)") (class "Default")
      (node (ref "IC20") (pin "18") (pinfunction "B4_18") (pintype "bidirectional"))
      (node (ref "R67") (pin "2") (pinfunction "2_2") (pintype "passive"))
    )
    (net (code "117") (name "Net-(IC20-B5)") (class "Default")
      (node (ref "IC20") (pin "17") (pinfunction "B5_17") (pintype "bidirectional"))
      (node (ref "R68") (pin "2") (pinfunction "2_2") (pintype "passive"))
    )
    (net (code "118") (name "Net-(IC20-B6)") (class "Default")
      (node (ref "IC20") (pin "16") (pinfunction "B6_16") (pintype "bidirectional"))
      (node (ref "R69") (pin "2") (pinfunction "2_2") (pintype "passive"))
    )
    (net (code "119") (name "Net-(IC20-B7)") (class "Default")
      (node (ref "IC20") (pin "15") (pinfunction "B7_15") (pintype "bidirectional"))
      (node (ref "R70") (pin "2") (pinfunction "2_2") (pintype "passive"))
    )
    (net (code "120") (name "Net-(IC20-B8)") (class "Default")
      (node (ref "IC20") (pin "14") (pinfunction "B8_14") (pintype "bidirectional"))
      (node (ref "R71") (pin "2") (pinfunction "2_2") (pintype "passive"))
    )
    (net (code "121") (name "Net-(LD1-A)") (class "Default")
      (node (ref "LD1") (pin "2") (pinfunction "A_2") (pintype "passive"))
      (node (ref "R70") (pin "1") (pinfunction "1_1") (pintype "passive"))
    )
    (net (code "122") (name "Net-(LD2-A)") (class "Default")
      (node (ref "LD2") (pin "2") (pinfunction "A_2") (pintype "passive"))
      (node (ref "R66") (pin "1") (pinfunction "1_1") (pintype "passive"))
    )
    (net (code "123") (name "Net-(LD3-A)") (class "Default")
      (node (ref "LD3") (pin "2") (pinfunction "A_2") (pintype "passive"))
      (node (ref "R60") (pin "1") (pinfunction "1_1") (pintype "passive"))
    )
    (net (code "124") (name "Net-(LD4-A)") (class "Default")
      (node (ref "LD4") (pin "2") (pinfunction "A_2") (pintype "passive"))
      (node (ref "R67") (pin "1") (pinfunction "1_1") (pintype "passive"))
    )
    (net (code "125") (name "Net-(LD5-A)") (class "Default")
      (node (ref "LD5") (pin "2") (pinfunction "A_2") (pintype "passive"))
      (node (ref "R65") (pin "1") (pinfunction "1_1") (pintype "passive"))
    )
    (net (code "126") (name "Net-(LD6-A)") (class "Default")
      (node (ref "LD6") (pin "2") (pinfunction "A_2") (pintype "passive"))
      (node (ref "R69") (pin "1") (pinfunction "1_1") (pintype "passive"))
    )
    (net (code "127") (name "Net-(LD7-A)") (class "Default")
      (node (ref "LD7") (pin "2") (pinfunction "A_2") (pintype "passive"))
      (node (ref "R71") (pin "1") (pinfunction "1_1") (pintype "passive"))
    )
    (net (code "128") (name "Net-(LD8-A)") (class "Default")
      (node (ref "LD8") (pin "2") (pinfunction "A_2") (pintype "passive"))
      (node (ref "R68") (pin "1") (pinfunction "1_1") (pintype "passive"))
    )
    (net (code "129") (name "Net-(T1-B)") (class "Default")
      (node (ref "R98") (pin "2") (pinfunction "2_2") (pintype "passive"))
      (node (ref "T1") (pin "1") (pinfunction "B_1") (pintype "passive"))
    )
    (net (code "130") (name "P1V8") (class "Default")
      (node (ref "C104") (pin "2") (pinfunction "2_2") (pintype "passive"))
      (node (ref "IC17") (pin "5") (pinfunction "VOUT_5") (pintype "power_in"))
      (node (ref "IC20") (pin "1") (pinfunction "VCCA_1") (pintype "power_in"))
      (node (ref "IC20") (pin "2") (pinfunction "DIR_2") (pintype "input"))
    )
    (net (code "131") (name "P2V5") (class "Default")
      (node (ref "IC4") (pin "1") (pinfunction "VCCA_1") (pintype "power_in"))
      (node (ref "IC4") (pin "2") (pinfunction "DIR_2") (pintype "input"))
    )
    (net (code "132") (name "P3V3") (class "Default")
      (node (ref "C87") (pin "2") (pinfunction "2_2") (pintype "passive"))
      (node (ref "IC17") (pin "1") (pinfunction "VIN_1") (pintype "input"))
      (node (ref "IC17") (pin "3") (pinfunction "VEN_3") (pintype "input"))
      (node (ref "IC20") (pin "23") (pinfunction "VCCB_23") (pintype "power_in"))
      (node (ref "IC20") (pin "24") (pinfunction "VCCB_24") (pintype "power_in"))
      (node (ref "IC4") (pin "23") (pinfunction "VCCB_23") (pintype "power_in"))
      (node (ref "IC4") (pin "24") (pinfunction "VCCB_24") (pintype "power_in"))
      (node (ref "TP10") (pin "1") (pinfunction "1_1") (pintype "bidirectional"))
    )
    (net (code "133") (name "P6V0A") (class "Default")
      (node (ref "TP8") (pin "1") (pinfunction "1_1") (pintype "bidirectional"))
    )
    (net (code "134") (name "P11V5A") (class "Default")
      (node (ref "TP6") (pin "1") (pinfunction "1_1") (pintype "bidirectional"))
    )
    (net (code "135") (name "unconnected-(IC17-NC-Pad4)") (class "Default")
      (node (ref "IC17") (pin "4") (pinfunction "NC_4") (pintype "passive+no_connect"))
    )
  )
)
